# 04151_lcdi2c.net
KiCad netlist of a schematic drawn in EAGLE
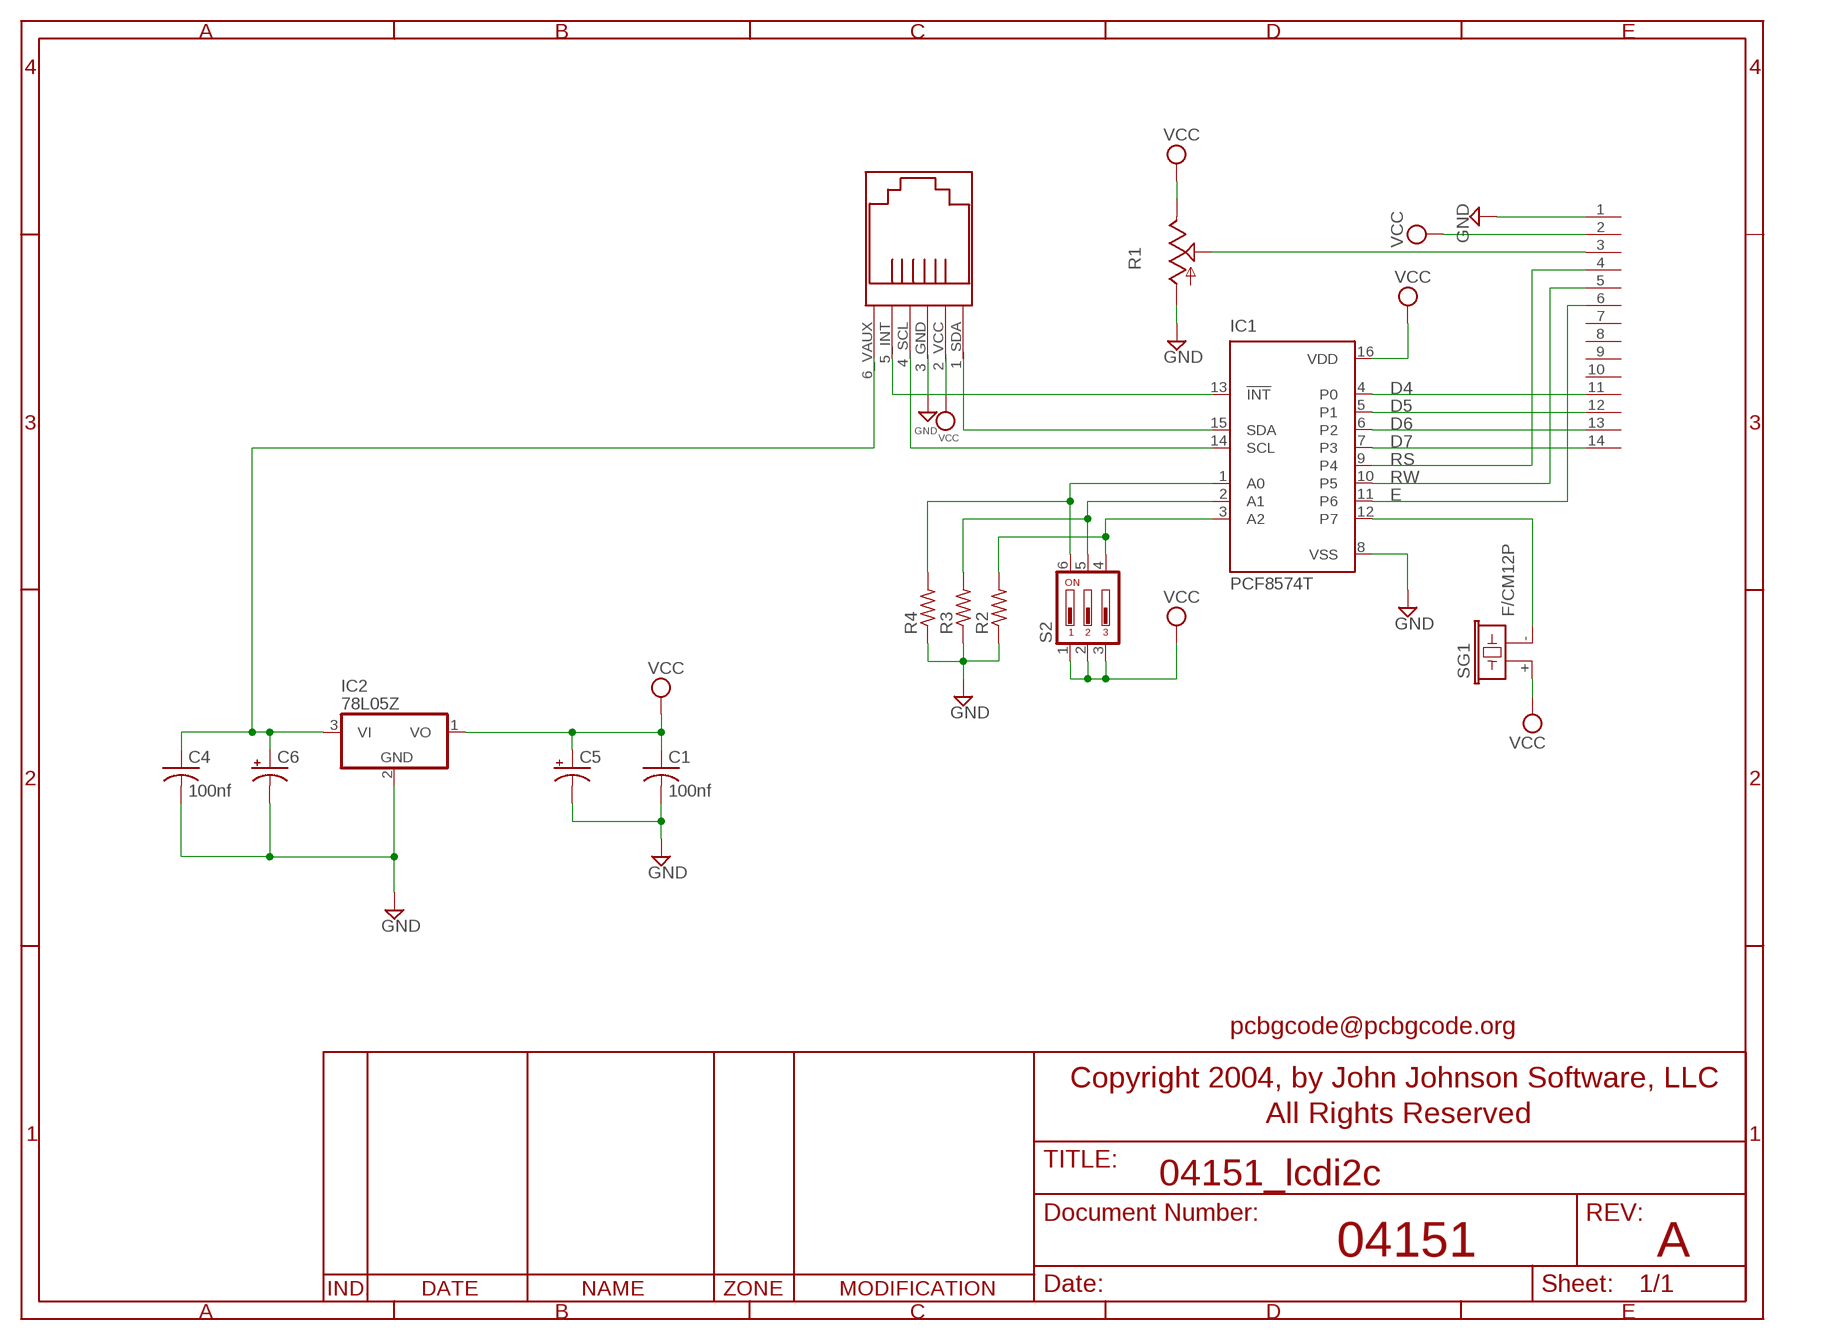
[diagram p0: schematic, sheet 1]

(export (version "E")
  (design (tool "Eeschema 10.0.6"))
  (components
    (comp (ref "C1")
      (value "100nf")
      (footprint "eagle-import:C1206")
      (libsource (lib "eagle-import") (part "C-USC1206"))
    )
    (comp (ref "C4")
      (value "100nf")
      (footprint "eagle-import:C1206")
      (libsource (lib "eagle-import") (part "C-USC1206"))
    )
    (comp (ref "C5")
      (value "CPOL-US!FAT_E2,5-5")
      (footprint "eagle-import:!FAT_E2,5-5")
      (libsource (lib "eagle-import") (part "CPOL-US!FAT_E2,5-5"))
    )
    (comp (ref "C6")
      (value "CPOL-US!FAT_E2,5-5")
      (footprint "eagle-import:!FAT_E2,5-5")
      (libsource (lib "eagle-import") (part "CPOL-US!FAT_E2,5-5"))
    )
    (comp (ref "IC1")
      (value "PCF8574T")
      (footprint "eagle-import:SO16W")
      (libsource (lib "eagle-import") (part "PCF8574T"))
    )
    (comp (ref "IC2")
      (value "78L05Z")
      (footprint "eagle-import:TO92")
      (libsource (lib "eagle-import") (part "78ZL05"))
    )
    (comp (ref "R1")
      (value "TRIM_US-PT-SPIN")
      (footprint "eagle-import:PT-SPIN")
      (libsource (lib "eagle-import") (part "TRIM_US-PT-SPIN"))
    )
    (comp (ref "R2")
      (value "R-US_R1206")
      (footprint "eagle-import:R1206")
      (libsource (lib "eagle-import") (part "R-US_R1206"))
    )
    (comp (ref "R3")
      (value "R-US_R1206")
      (footprint "eagle-import:R1206")
      (libsource (lib "eagle-import") (part "R-US_R1206"))
    )
    (comp (ref "R4")
      (value "R-US_R1206")
      (footprint "eagle-import:R1206")
      (libsource (lib "eagle-import") (part "R-US_R1206"))
    )
    (comp (ref "S2")
      (value "DIP03YL")
      (footprint "eagle-import:DIP03YL")
      (libsource (lib "eagle-import") (part "DIP03YL"))
    )
    (comp (ref "SG1")
      (value "F/CM12P")
      (footprint "eagle-import:F_CM12P")
      (libsource (lib "eagle-import") (part "F/CM12P"))
    )
    (comp (ref "U$1")
      (value "RJ-12")
      (footprint "eagle-import:RJ-12")
      (libsource (lib "eagle-import") (part "RJ-12"))
    )
    (comp (ref "U$2")
      (value "MA07-2-SGL")
      (footprint "eagle-import:MA07-2")
      (libsource (lib "eagle-import") (part "MA07-2-SGL"))
    )
  )
  (nets
    (net (code "1") (name "/D4") (class "Default")
      (node (ref "IC1") (pin "4") (pinfunction "P0_4") (pintype "bidirectional"))
      (node (ref "U$2") (pin "11") (pinfunction "11_11") (pintype "passive"))
    )
    (net (code "2") (name "/D5") (class "Default")
      (node (ref "IC1") (pin "5") (pinfunction "P1_5") (pintype "bidirectional"))
      (node (ref "U$2") (pin "12") (pinfunction "12_12") (pintype "passive"))
    )
    (net (code "3") (name "/D6") (class "Default")
      (node (ref "IC1") (pin "6") (pinfunction "P2_6") (pintype "bidirectional"))
      (node (ref "U$2") (pin "13") (pinfunction "13_13") (pintype "passive"))
    )
    (net (code "4") (name "/D7") (class "Default")
      (node (ref "IC1") (pin "7") (pinfunction "P3_7") (pintype "bidirectional"))
      (node (ref "U$2") (pin "14") (pinfunction "14_14") (pintype "passive"))
    )
    (net (code "5") (name "/E") (class "Default")
      (node (ref "IC1") (pin "11") (pinfunction "P6_11") (pintype "bidirectional"))
      (node (ref "U$2") (pin "6") (pinfunction "6_6") (pintype "passive"))
    )
    (net (code "6") (name "/RS") (class "Default")
      (node (ref "IC1") (pin "9") (pinfunction "P4_9") (pintype "bidirectional"))
      (node (ref "U$2") (pin "4") (pinfunction "4_4") (pintype "passive"))
    )
    (net (code "7") (name "/RW") (class "Default")
      (node (ref "IC1") (pin "10") (pinfunction "P5_10") (pintype "bidirectional"))
      (node (ref "U$2") (pin "5") (pinfunction "5_5") (pintype "passive"))
    )
    (net (code "8") (name "GND") (class "Default")
      (node (ref "C1") (pin "2") (pinfunction "2_2") (pintype "passive"))
      (node (ref "C4") (pin "2") (pinfunction "2_2") (pintype "passive"))
      (node (ref "C5") (pin "P$2") (pinfunction "-_P$2") (pintype "passive"))
      (node (ref "C6") (pin "P$2") (pinfunction "-_P$2") (pintype "passive"))
      (node (ref "IC1") (pin "8") (pinfunction "VSS_8") (pintype "power_in"))
      (node (ref "IC2") (pin "2") (pinfunction "GND_2") (pintype "passive"))
      (node (ref "R1") (pin "A") (pinfunction "A_A") (pintype "passive"))
      (node (ref "R2") (pin "1") (pinfunction "1_1") (pintype "passive"))
      (node (ref "R3") (pin "1") (pinfunction "1_1") (pintype "passive"))
      (node (ref "R4") (pin "1") (pinfunction "1_1") (pintype "passive"))
      (node (ref "U$1") (pin "3_GND") (pinfunction "3_GND_3_GND") (pintype "bidirectional"))
      (node (ref "U$2") (pin "1") (pinfunction "1_1") (pintype "passive"))
    )
    (net (code "9") (name "Net-(C6-+)") (class "Default")
      (node (ref "C4") (pin "1") (pinfunction "1_1") (pintype "passive"))
      (node (ref "C6") (pin "P$1") (pinfunction "+_P$1") (pintype "passive"))
      (node (ref "IC2") (pin "3") (pinfunction "VI_3") (pintype "input"))
      (node (ref "U$1") (pin "6_VAUX") (pinfunction "6_VAUX_6_VAUX") (pintype "bidirectional"))
    )
    (net (code "10") (name "Net-(IC1-A0)") (class "Default")
      (node (ref "IC1") (pin "1") (pinfunction "A0_1") (pintype "input"))
      (node (ref "R4") (pin "2") (pinfunction "2_2") (pintype "passive"))
      (node (ref "S2") (pin "6") (pinfunction "6_6") (pintype "passive"))
    )
    (net (code "11") (name "Net-(IC1-A1)") (class "Default")
      (node (ref "IC1") (pin "2") (pinfunction "A1_2") (pintype "input"))
      (node (ref "R3") (pin "2") (pinfunction "2_2") (pintype "passive"))
      (node (ref "S2") (pin "5") (pinfunction "5_5") (pintype "passive"))
    )
    (net (code "12") (name "Net-(IC1-A2)") (class "Default")
      (node (ref "IC1") (pin "3") (pinfunction "A2_3") (pintype "input"))
      (node (ref "R2") (pin "2") (pinfunction "2_2") (pintype "passive"))
      (node (ref "S2") (pin "4") (pinfunction "4_4") (pintype "passive"))
    )
    (net (code "13") (name "Net-(IC1-P7)") (class "Default")
      (node (ref "IC1") (pin "12") (pinfunction "P7_12") (pintype "bidirectional"))
      (node (ref "SG1") (pin "-") (pinfunction "2_-") (pintype "passive"))
    )
    (net (code "14") (name "Net-(IC1-SCL)") (class "Default")
      (node (ref "IC1") (pin "14") (pinfunction "SCL_14") (pintype "input"))
      (node (ref "U$1") (pin "4_SCL") (pinfunction "4_SCL_4_SCL") (pintype "bidirectional"))
    )
    (net (code "15") (name "Net-(IC1-SDA)") (class "Default")
      (node (ref "IC1") (pin "15") (pinfunction "SDA_15") (pintype "bidirectional"))
      (node (ref "U$1") (pin "1_SDA") (pinfunction "1_SDA_1_SDA") (pintype "bidirectional"))
    )
    (net (code "16") (name "Net-(IC1-~{INT})") (class "Default")
      (node (ref "IC1") (pin "13") (pinfunction "~{INT}_13") (pintype "output"))
      (node (ref "U$1") (pin "5_INT") (pinfunction "5_INT_5_INT") (pintype "bidirectional"))
    )
    (net (code "17") (name "Net-(R1-PadS)") (class "Default")
      (node (ref "R1") (pin "S") (pinfunction "S_S") (pintype "passive"))
      (node (ref "U$2") (pin "3") (pinfunction "3_3") (pintype "passive"))
    )
    (net (code "18") (name "VCC") (class "Default")
      (node (ref "C1") (pin "1") (pinfunction "1_1") (pintype "passive"))
      (node (ref "C5") (pin "P$1") (pinfunction "+_P$1") (pintype "passive"))
      (node (ref "IC1") (pin "16") (pinfunction "VDD_16") (pintype "power_in"))
      (node (ref "IC2") (pin "1") (pinfunction "VO_1") (pintype "passive"))
      (node (ref "R1") (pin "E") (pinfunction "E_E") (pintype "passive"))
      (node (ref "S2") (pin "1") (pinfunction "1_1") (pintype "passive"))
      (node (ref "S2") (pin "2") (pinfunction "2_2") (pintype "passive"))
      (node (ref "S2") (pin "3") (pinfunction "3_3") (pintype "passive"))
      (node (ref "SG1") (pin "+") (pinfunction "1_+") (pintype "passive"))
      (node (ref "U$1") (pin "2_VCC") (pinfunction "2_VCC_2_VCC") (pintype "bidirectional"))
      (node (ref "U$2") (pin "2") (pinfunction "2_2") (pintype "passive"))
    )
    (net (code "19") (name "unconnected-(U$2-Pad7)") (class "Default")
      (node (ref "U$2") (pin "7") (pinfunction "7_7") (pintype "passive"))
    )
    (net (code "20") (name "unconnected-(U$2-Pad8)") (class "Default")
      (node (ref "U$2") (pin "8") (pinfunction "8_8") (pintype "passive"))
    )
    (net (code "21") (name "unconnected-(U$2-Pad9)") (class "Default")
      (node (ref "U$2") (pin "9") (pinfunction "9_9") (pintype "passive"))
    )
    (net (code "22") (name "unconnected-(U$2-Pad10)") (class "Default")
      (node (ref "U$2") (pin "10") (pinfunction "10_10") (pintype "passive"))
    )
  )
)
